# Esp8266-01_Luxmetre.net
KiCad netlist of a schematic drawn in EAGLE
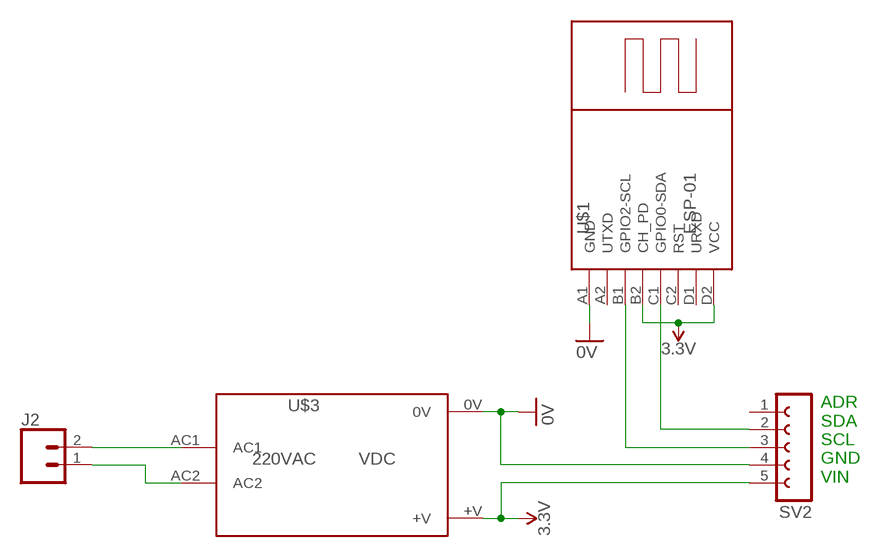
[diagram p0: schematic, sheet 1]

(export (version "E")
  (design (tool "Eeschema 10.0.6"))
  (components
    (comp (ref "J2")
      (value "CONN_025MM")
      (footprint "eagle-import:BORNIER_A_VIS_2_5.12MM")
      (libsource (lib "eagle-import") (part "CONN_025MM"))
    )
    (comp (ref "SV2")
      (value "FE05-1")
      (footprint "eagle-import:FE05-1")
      (libsource (lib "eagle-import") (part "FE05-1"))
    )
    (comp (ref "U$1")
      (value "ESP-01")
      (footprint "eagle-import:ESP-01")
      (libsource (lib "eagle-import") (part "ESP-01"))
    )
    (comp (ref "U$3")
      (value "TSP05-5V-3W")
      (footprint "eagle-import:TSP05-VDC-3W")
      (libsource (lib "eagle-import") (part "TSP05-5V-3W"))
    )
  )
  (nets
    (net (code "1") (name "0V") (class "Default")
      (node (ref "SV2") (pin "4") (pinfunction "4_4") (pintype "passive"))
      (node (ref "U$1") (pin "A1") (pinfunction "GND_A1") (pintype "power_in"))
      (node (ref "U$3") (pin "0V") (pinfunction "0V_0V") (pintype "output"))
    )
    (net (code "2") (name "3.3V") (class "Default")
      (node (ref "SV2") (pin "5") (pinfunction "5_5") (pintype "passive"))
      (node (ref "U$1") (pin "B2") (pinfunction "CH_PD_B2") (pintype "bidirectional"))
      (node (ref "U$1") (pin "D2") (pinfunction "VCC_D2") (pintype "power_in"))
      (node (ref "U$3") (pin "+V") (pinfunction "+V_+V") (pintype "output"))
    )
    (net (code "3") (name "Net-(J2-Pad1)") (class "Default")
      (node (ref "J2") (pin "1") (pinfunction "1_1") (pintype "passive"))
      (node (ref "U$3") (pin "AC2") (pinfunction "AC2_AC2") (pintype "input"))
    )
    (net (code "4") (name "Net-(J2-Pad2)") (class "Default")
      (node (ref "J2") (pin "2") (pinfunction "2_2") (pintype "passive"))
      (node (ref "U$3") (pin "AC1") (pinfunction "AC1_AC1") (pintype "bidirectional"))
    )
    (net (code "5") (name "Net-(U$1-GPIO0-SDA)") (class "Default")
      (node (ref "SV2") (pin "2") (pinfunction "2_2") (pintype "passive"))
      (node (ref "U$1") (pin "C1") (pinfunction "GPIO0-SDA_C1") (pintype "bidirectional"))
    )
    (net (code "6") (name "Net-(U$1-GPIO2-SCL)") (class "Default")
      (node (ref "SV2") (pin "3") (pinfunction "3_3") (pintype "passive"))
      (node (ref "U$1") (pin "B1") (pinfunction "GPIO2-SCL_B1") (pintype "bidirectional"))
    )
    (net (code "7") (name "unconnected-(SV2-Pad1)") (class "Default")
      (node (ref "SV2") (pin "1") (pinfunction "1_1") (pintype "passive"))
    )
    (net (code "8") (name "unconnected-(U$1-RST-PadC2)") (class "Default")
      (node (ref "U$1") (pin "C2") (pinfunction "RST_C2") (pintype "bidirectional"))
    )
    (net (code "9") (name "unconnected-(U$1-URXD-PadD1)") (class "Default")
      (node (ref "U$1") (pin "D1") (pinfunction "URXD_D1") (pintype "bidirectional"))
    )
    (net (code "10") (name "unconnected-(U$1-UTXD-PadA2)") (class "Default")
      (node (ref "U$1") (pin "A2") (pinfunction "UTXD_A2") (pintype "bidirectional"))
    )
  )
)
